# zero-tiny-ble.net
KiCad netlist of a schematic drawn in EAGLE
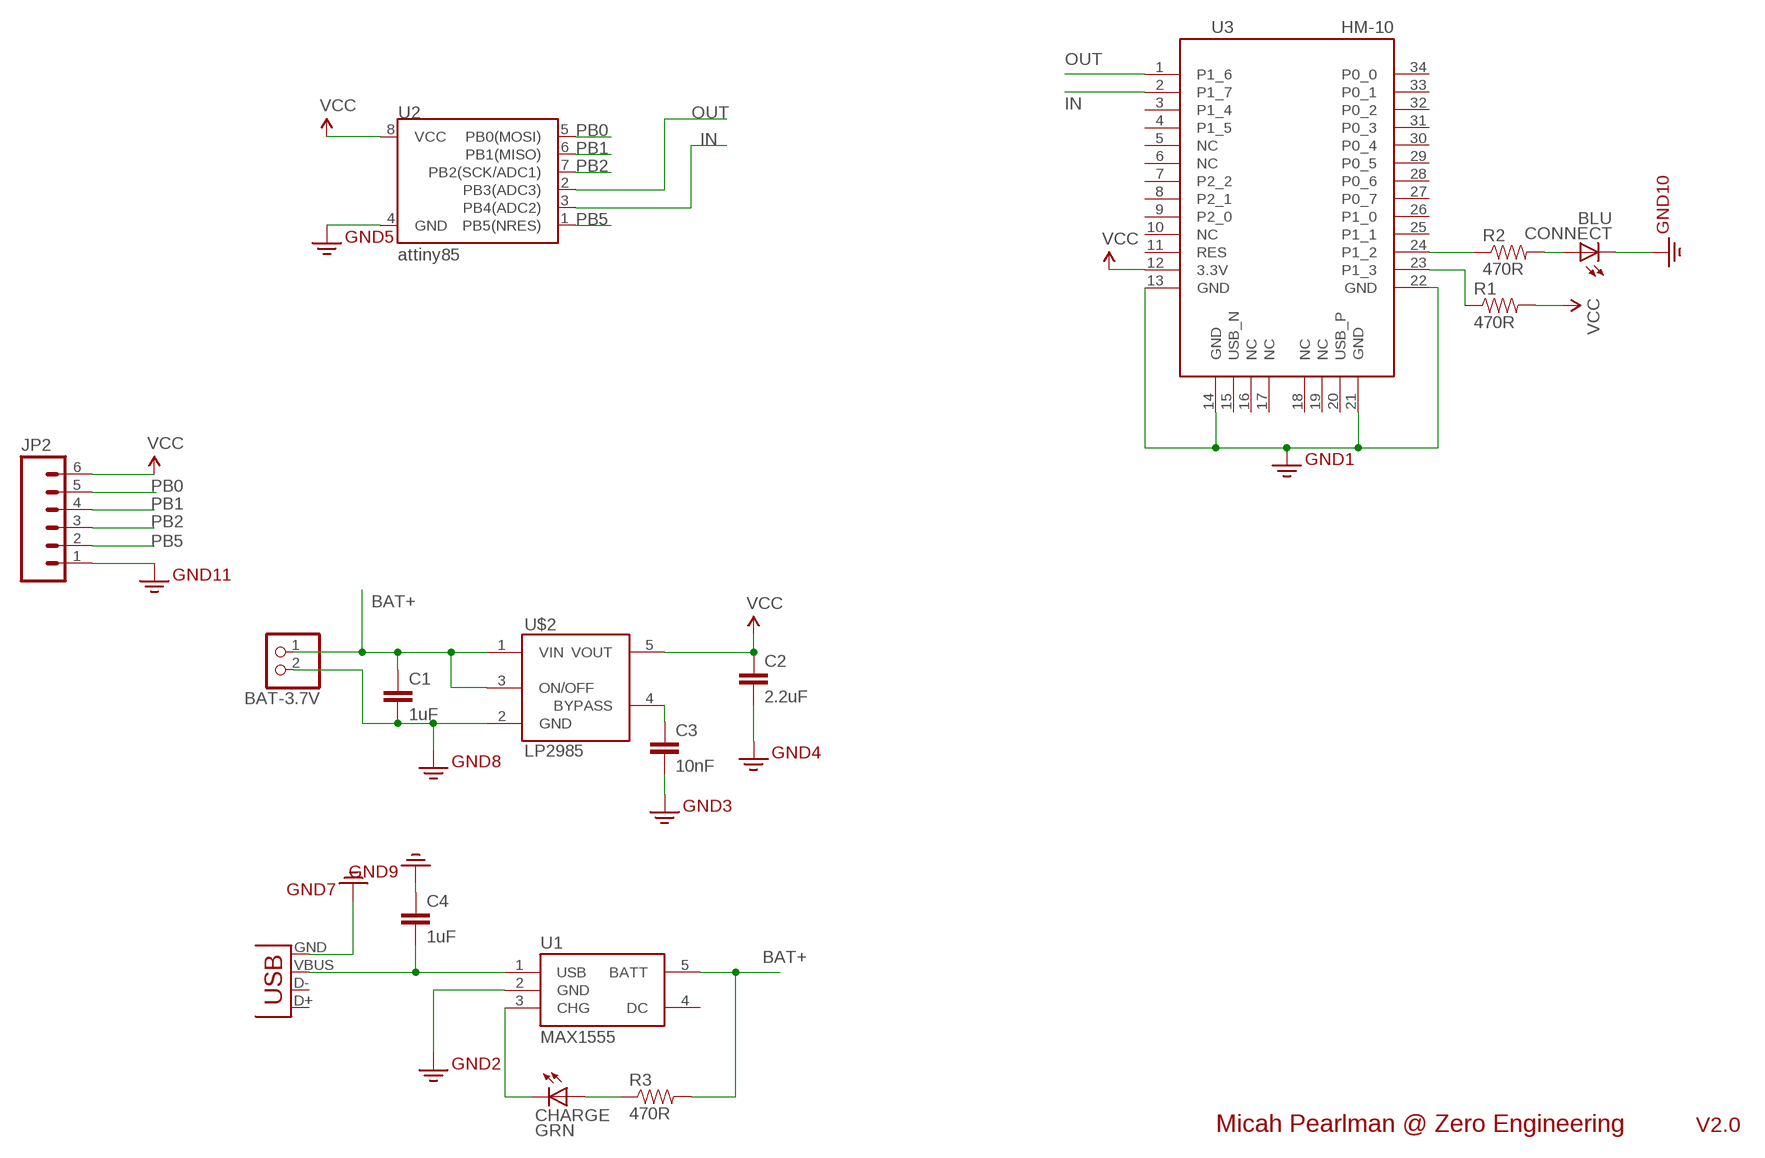
[diagram p0: schematic, sheet 1]

(export (version "E")
  (design (tool "Eeschema 10.0.6"))
  (components
    (comp (ref "BAT-3.7V")
      (value "JST_2PIN-THM")
      (footprint "eagle-import:JST-PH-2-THM")
      (libsource (lib "eagle-import") (part "JST_2PIN-THM"))
    )
    (comp (ref "C1")
      (value "1uF")
      (footprint "eagle-import:0805")
      (libsource (lib "eagle-import") (part "1UF-25V-10%(0805)"))
    )
    (comp (ref "C2")
      (value "2.2uF")
      (footprint "eagle-import:0805")
      (libsource (lib "eagle-import") (part "2.2UF-25V-+80/-20(0805)"))
    )
    (comp (ref "C3")
      (value "10nF")
      (footprint "eagle-import:0805")
      (libsource (lib "eagle-import") (part "CAP0805"))
    )
    (comp (ref "C4")
      (value "1uF")
      (footprint "eagle-import:0805")
      (libsource (lib "eagle-import") (part "1UF-25V-10%(0805)"))
    )
    (comp (ref "CHARGE")
      (value "GRN")
      (footprint "eagle-import:CHIPLED_0805")
      (libsource (lib "eagle-import") (part "LEDCHIPLED_0805"))
    )
    (comp (ref "CONNECT")
      (value "BLU")
      (footprint "eagle-import:CHIPLED_0805")
      (libsource (lib "eagle-import") (part "LEDCHIPLED_0805"))
    )
    (comp (ref "JP1")
      (value "USB-SMD-NS")
      (footprint "eagle-import:USB-MINIB-NOSTOP")
      (libsource (lib "eagle-import") (part "USB-SMD-NS"))
    )
    (comp (ref "JP2")
      (value "M06SILK_FEMALE_PTH")
      (footprint "eagle-import:1X06")
      (libsource (lib "eagle-import") (part "M06SILK_FEMALE_PTH"))
    )
    (comp (ref "R1")
      (value "470R")
      (footprint "eagle-import:0805")
      (libsource (lib "eagle-import") (part "0.3OHM-1/8W-1%(0805)"))
    )
    (comp (ref "R2")
      (value "470R")
      (footprint "eagle-import:0805")
      (libsource (lib "eagle-import") (part "0.3OHM-1/8W-1%(0805)"))
    )
    (comp (ref "R3")
      (value "470R")
      (footprint "eagle-import:0805")
      (libsource (lib "eagle-import") (part "0.3OHM-1/8W-1%(0805)"))
    )
    (comp (ref "U$2")
      (value "LP2985AIM5-3.3")
      (footprint "eagle-import:SOT25")
      (libsource (lib "eagle-import") (part "LP2985AIM5-3.3"))
    )
    (comp (ref "U1")
      (value "MAX1555")
      (footprint "eagle-import:SOT23-5")
      (libsource (lib "eagle-import") (part "MAX1555"))
    )
    (comp (ref "U2")
      (value "attiny85")
      (footprint "eagle-import:DIP08")
      (libsource (lib "eagle-import") (part "ATTINY45TINY85-20-DIP"))
    )
    (comp (ref "U3")
      (value "HM-10")
      (footprint "eagle-import:HM-10")
      (libsource (lib "eagle-import") (part "HM-10"))
    )
  )
  (nets
    (net (code "1") (name "/BAT+") (class "Default")
      (node (ref "BAT-3.7V") (pin "1") (pinfunction "2_1") (pintype "passive"))
      (node (ref "C1") (pin "1") (pinfunction "1_1") (pintype "passive"))
      (node (ref "R3") (pin "2") (pinfunction "2_2") (pintype "passive"))
      (node (ref "U$2") (pin "1") (pinfunction "VIN_1") (pintype "power_in"))
      (node (ref "U$2") (pin "3") (pinfunction "ON/OFF_3") (pintype "input"))
      (node (ref "U1") (pin "5") (pinfunction "BATT_5") (pintype "bidirectional"))
    )
    (net (code "2") (name "/IN") (class "Default")
      (node (ref "U2") (pin "3") (pinfunction "PB4(ADC2)_3") (pintype "bidirectional"))
      (node (ref "U3") (pin "2") (pinfunction "P1_7_2") (pintype "bidirectional"))
    )
    (net (code "3") (name "/OUT") (class "Default")
      (node (ref "U2") (pin "2") (pinfunction "PB3(ADC3)_2") (pintype "bidirectional"))
      (node (ref "U3") (pin "1") (pinfunction "P1_6_1") (pintype "bidirectional"))
    )
    (net (code "4") (name "/PB0") (class "Default")
      (node (ref "JP2") (pin "5") (pinfunction "5_5") (pintype "passive"))
      (node (ref "U2") (pin "5") (pinfunction "PB0(MOSI)_5") (pintype "bidirectional"))
    )
    (net (code "5") (name "/PB1") (class "Default")
      (node (ref "JP2") (pin "4") (pinfunction "4_4") (pintype "passive"))
      (node (ref "U2") (pin "6") (pinfunction "PB1(MISO)_6") (pintype "bidirectional"))
    )
    (net (code "6") (name "/PB2") (class "Default")
      (node (ref "JP2") (pin "3") (pinfunction "3_3") (pintype "passive"))
      (node (ref "U2") (pin "7") (pinfunction "PB2(SCK/ADC1)_7") (pintype "bidirectional"))
    )
    (net (code "7") (name "/PB5") (class "Default")
      (node (ref "JP2") (pin "2") (pinfunction "2_2") (pintype "passive"))
      (node (ref "U2") (pin "1") (pinfunction "PB5(NRES)_1") (pintype "bidirectional"))
    )
    (net (code "8") (name "GND2") (class "Default")
      (node (ref "BAT-3.7V") (pin "2") (pinfunction "1_2") (pintype "passive"))
      (node (ref "C1") (pin "2") (pinfunction "2_2") (pintype "passive"))
      (node (ref "C2") (pin "2") (pinfunction "2_2") (pintype "passive"))
      (node (ref "C3") (pin "2") (pinfunction "2_2") (pintype "passive"))
      (node (ref "C4") (pin "1") (pinfunction "1_1") (pintype "passive"))
      (node (ref "CONNECT") (pin "C") (pinfunction "C_C") (pintype "passive"))
      (node (ref "JP1") (pin "GND") (pinfunction "GND_GND") (pintype "bidirectional"))
      (node (ref "JP2") (pin "1") (pinfunction "1_1") (pintype "passive"))
      (node (ref "U$2") (pin "2") (pinfunction "GND_2") (pintype "power_in"))
      (node (ref "U1") (pin "2") (pinfunction "GND_2") (pintype "bidirectional"))
      (node (ref "U2") (pin "4") (pinfunction "GND_4") (pintype "bidirectional"))
      (node (ref "U3") (pin "13") (pinfunction "GND_13") (pintype "bidirectional"))
      (node (ref "U3") (pin "14") (pinfunction "GND_14") (pintype "bidirectional"))
      (node (ref "U3") (pin "21") (pinfunction "GND_21") (pintype "bidirectional"))
      (node (ref "U3") (pin "22") (pinfunction "GND_22") (pintype "bidirectional"))
    )
    (net (code "9") (name "Net-(CHARGE-PadA)") (class "Default")
      (node (ref "CHARGE") (pin "A") (pinfunction "A_A") (pintype "passive"))
      (node (ref "R3") (pin "1") (pinfunction "1_1") (pintype "passive"))
    )
    (net (code "10") (name "Net-(CONNECT-PadA)") (class "Default")
      (node (ref "CONNECT") (pin "A") (pinfunction "A_A") (pintype "passive"))
      (node (ref "R2") (pin "2") (pinfunction "2_2") (pintype "passive"))
    )
    (net (code "11") (name "Net-(U$2-BYPASS)") (class "Default")
      (node (ref "C3") (pin "1") (pinfunction "1_1") (pintype "passive"))
      (node (ref "U$2") (pin "4") (pinfunction "BYPASS_4") (pintype "power_in"))
    )
    (net (code "12") (name "Net-(U1-CHG)") (class "Default")
      (node (ref "CHARGE") (pin "C") (pinfunction "C_C") (pintype "passive"))
      (node (ref "U1") (pin "3") (pinfunction "CHG_3") (pintype "bidirectional"))
    )
    (net (code "13") (name "Net-(U1-USB)") (class "Default")
      (node (ref "C4") (pin "2") (pinfunction "2_2") (pintype "passive"))
      (node (ref "JP1") (pin "VBUS") (pinfunction "VBUS_VBUS") (pintype "bidirectional"))
      (node (ref "U1") (pin "1") (pinfunction "USB_1") (pintype "bidirectional"))
    )
    (net (code "14") (name "Net-(U3-P1_2)") (class "Default")
      (node (ref "R2") (pin "1") (pinfunction "1_1") (pintype "passive"))
      (node (ref "U3") (pin "24") (pinfunction "P1_2_24") (pintype "bidirectional"))
    )
    (net (code "15") (name "Net-(U3-P1_3)") (class "Default")
      (node (ref "R1") (pin "1") (pinfunction "1_1") (pintype "passive"))
      (node (ref "U3") (pin "23") (pinfunction "P1_3_23") (pintype "bidirectional"))
    )
    (net (code "16") (name "VCC") (class "Default")
      (node (ref "C2") (pin "1") (pinfunction "1_1") (pintype "passive"))
      (node (ref "JP2") (pin "6") (pinfunction "6_6") (pintype "passive"))
      (node (ref "R1") (pin "2") (pinfunction "2_2") (pintype "passive"))
      (node (ref "U$2") (pin "5") (pinfunction "VOUT_5") (pintype "power_in"))
      (node (ref "U2") (pin "8") (pinfunction "VCC_8") (pintype "bidirectional"))
      (node (ref "U3") (pin "12") (pinfunction "3.3V_12") (pintype "bidirectional"))
    )
    (net (code "17") (name "unconnected-(JP1-PadD+)") (class "Default")
      (node (ref "JP1") (pin "D+") (pinfunction "D+_D+") (pintype "bidirectional"))
    )
    (net (code "18") (name "unconnected-(JP1-PadD-)") (class "Default")
      (node (ref "JP1") (pin "D-") (pinfunction "D-_D-") (pintype "bidirectional"))
    )
    (net (code "19") (name "unconnected-(U1-DC-Pad4)") (class "Default")
      (node (ref "U1") (pin "4") (pinfunction "DC_4") (pintype "bidirectional"))
    )
    (net (code "20") (name "unconnected-(U3-NC-Pad5)") (class "Default")
      (node (ref "U3") (pin "5") (pinfunction "NC_5") (pintype "bidirectional"))
    )
    (net (code "21") (name "unconnected-(U3-NC-Pad6)") (class "Default")
      (node (ref "U3") (pin "6") (pinfunction "NC_6") (pintype "bidirectional"))
    )
    (net (code "22") (name "unconnected-(U3-NC-Pad10)") (class "Default")
      (node (ref "U3") (pin "10") (pinfunction "NC_10") (pintype "bidirectional"))
    )
    (net (code "23") (name "unconnected-(U3-NC-Pad16)") (class "Default")
      (node (ref "U3") (pin "16") (pinfunction "NC_16") (pintype "bidirectional"))
    )
    (net (code "24") (name "unconnected-(U3-NC-Pad17)") (class "Default")
      (node (ref "U3") (pin "17") (pinfunction "NC_17") (pintype "bidirectional"))
    )
    (net (code "25") (name "unconnected-(U3-NC-Pad18)") (class "Default")
      (node (ref "U3") (pin "18") (pinfunction "NC_18") (pintype "bidirectional"))
    )
    (net (code "26") (name "unconnected-(U3-NC-Pad19)") (class "Default")
      (node (ref "U3") (pin "19") (pinfunction "NC_19") (pintype "bidirectional"))
    )
    (net (code "27") (name "unconnected-(U3-P0_0-Pad34)") (class "Default")
      (node (ref "U3") (pin "34") (pinfunction "P0_0_34") (pintype "bidirectional"))
    )
    (net (code "28") (name "unconnected-(U3-P0_1-Pad33)") (class "Default")
      (node (ref "U3") (pin "33") (pinfunction "P0_1_33") (pintype "bidirectional"))
    )
    (net (code "29") (name "unconnected-(U3-P0_2-Pad32)") (class "Default")
      (node (ref "U3") (pin "32") (pinfunction "P0_2_32") (pintype "bidirectional"))
    )
    (net (code "30") (name "unconnected-(U3-P0_3-Pad31)") (class "Default")
      (node (ref "U3") (pin "31") (pinfunction "P0_3_31") (pintype "bidirectional"))
    )
    (net (code "31") (name "unconnected-(U3-P0_4-Pad30)") (class "Default")
      (node (ref "U3") (pin "30") (pinfunction "P0_4_30") (pintype "bidirectional"))
    )
    (net (code "32") (name "unconnected-(U3-P0_5-Pad29)") (class "Default")
      (node (ref "U3") (pin "29") (pinfunction "P0_5_29") (pintype "bidirectional"))
    )
    (net (code "33") (name "unconnected-(U3-P0_6-Pad28)") (class "Default")
      (node (ref "U3") (pin "28") (pinfunction "P0_6_28") (pintype "bidirectional"))
    )
    (net (code "34") (name "unconnected-(U3-P0_7-Pad27)") (class "Default")
      (node (ref "U3") (pin "27") (pinfunction "P0_7_27") (pintype "bidirectional"))
    )
    (net (code "35") (name "unconnected-(U3-P1_0-Pad26)") (class "Default")
      (node (ref "U3") (pin "26") (pinfunction "P1_0_26") (pintype "bidirectional"))
    )
    (net (code "36") (name "unconnected-(U3-P1_1-Pad25)") (class "Default")
      (node (ref "U3") (pin "25") (pinfunction "P1_1_25") (pintype "bidirectional"))
    )
    (net (code "37") (name "unconnected-(U3-P1_4-Pad3)") (class "Default")
      (node (ref "U3") (pin "3") (pinfunction "P1_4_3") (pintype "bidirectional"))
    )
    (net (code "38") (name "unconnected-(U3-P1_5-Pad4)") (class "Default")
      (node (ref "U3") (pin "4") (pinfunction "P1_5_4") (pintype "bidirectional"))
    )
    (net (code "39") (name "unconnected-(U3-P2_0-Pad9)") (class "Default")
      (node (ref "U3") (pin "9") (pinfunction "P2_0_9") (pintype "bidirectional"))
    )
    (net (code "40") (name "unconnected-(U3-P2_1-Pad8)") (class "Default")
      (node (ref "U3") (pin "8") (pinfunction "P2_1_8") (pintype "bidirectional"))
    )
    (net (code "41") (name "unconnected-(U3-P2_2-Pad7)") (class "Default")
      (node (ref "U3") (pin "7") (pinfunction "P2_2_7") (pintype "bidirectional"))
    )
    (net (code "42") (name "unconnected-(U3-RES-Pad11)") (class "Default")
      (node (ref "U3") (pin "11") (pinfunction "RES_11") (pintype "bidirectional"))
    )
    (net (code "43") (name "unconnected-(U3-USB_N-Pad15)") (class "Default")
      (node (ref "U3") (pin "15") (pinfunction "USB_N_15") (pintype "bidirectional"))
    )
    (net (code "44") (name "unconnected-(U3-USB_P-Pad20)") (class "Default")
      (node (ref "U3") (pin "20") (pinfunction "USB_P_20") (pintype "bidirectional"))
    )
  )
)
